# QCopterMV-Camera_Sch.net
KiCad netlist of a schematic drawn in Altium Designer
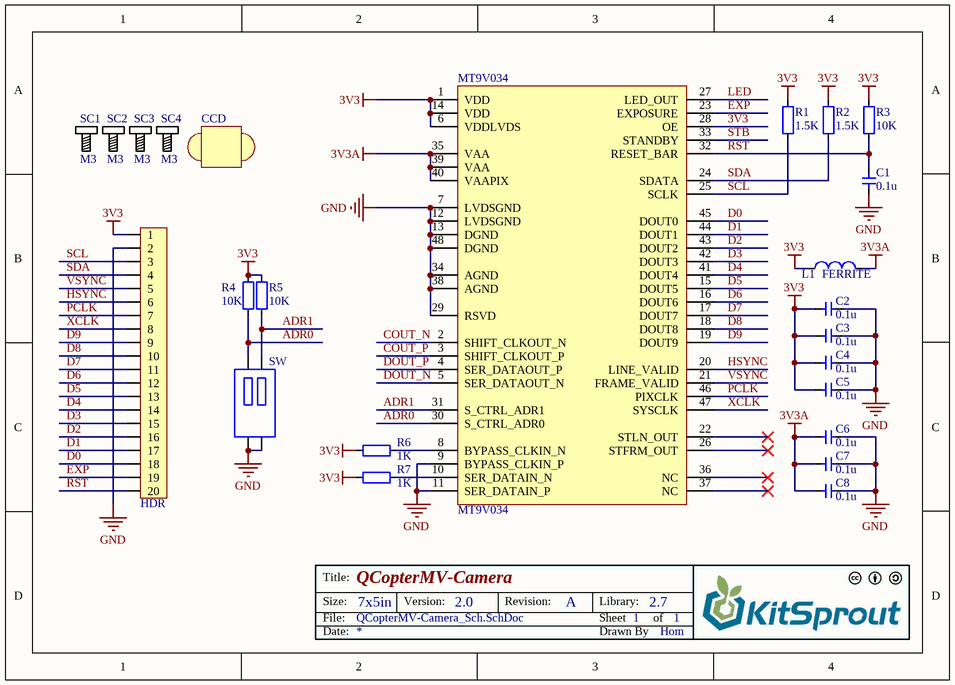
[diagram p0: QCopterMV-Camera_Sch.SchDoc]

(export (version "E")
  (design (tool "Eeschema 10.0.6"))
  (components
    (comp (ref "C1")
      (value "0.1u")
      (footprint "PCB_PassiveCap:CAP_0603")
      (description "Capacitor")
      (fields (field (name "Comment") "Cap_0603"))
      (libsource (lib "SCH_Passive") (part "Cap_0603"))
    )
    (comp (ref "C2")
      (value "0.1u")
      (footprint "PCB_PassiveCap:CAP_0603")
      (description "Capacitor")
      (fields (field (name "Comment") "Cap_0603"))
      (libsource (lib "SCH_Passive") (part "Cap_0603"))
    )
    (comp (ref "C3")
      (value "0.1u")
      (footprint "PCB_PassiveCap:CAP_0603")
      (description "Capacitor")
      (fields (field (name "Comment") "Cap_0603"))
      (libsource (lib "SCH_Passive") (part "Cap_0603"))
    )
    (comp (ref "C4")
      (value "0.1u")
      (footprint "PCB_PassiveCap:CAP_0603")
      (description "Capacitor")
      (fields (field (name "Comment") "Cap_0603"))
      (libsource (lib "SCH_Passive") (part "Cap_0603"))
    )
    (comp (ref "C5")
      (value "0.1u")
      (footprint "PCB_PassiveCap:CAP_0603")
      (description "Capacitor")
      (fields (field (name "Comment") "Cap_0603"))
      (libsource (lib "SCH_Passive") (part "Cap_0603"))
    )
    (comp (ref "C6")
      (value "0.1u")
      (footprint "PCB_PassiveCap:CAP_0603")
      (description "Capacitor")
      (fields (field (name "Comment") "Cap_0603"))
      (libsource (lib "SCH_Passive") (part "Cap_0603"))
    )
    (comp (ref "C7")
      (value "0.1u")
      (footprint "PCB_PassiveCap:CAP_0603")
      (description "Capacitor")
      (fields (field (name "Comment") "Cap_0603"))
      (libsource (lib "SCH_Passive") (part "Cap_0603"))
    )
    (comp (ref "C8")
      (value "0.1u")
      (footprint "PCB_PassiveCap:CAP_0603")
      (description "Capacitor")
      (fields (field (name "Comment") "Cap_0603"))
      (libsource (lib "SCH_Passive") (part "Cap_0603"))
    )
    (comp (ref "CCD")
      (value "CCD")
      (footprint "PCB_Mechanical:CCD_LENS_20MM")
      (libsource (lib "SCH_Mechanical") (part "lensCCD_20"))
    )
    (comp (ref "HDR")
      (value "HDR1x20_1.27")
      (footprint "PCB_ConnectorHDR:HDR1X20_1.27_180")
      (description "Header")
      (libsource (lib "SCH_ConnectorHDR") (part "HDR1x20_1.27"))
    )
    (comp (ref "L1")
      (value "FERRITE")
      (footprint "PCB_PassiveInd:IND_0603")
      (description "Inductor")
      (fields (field (name "Comment") "Ind_0603"))
      (libsource (lib "SCH_Passive") (part "Ind_0603"))
    )
    (comp (ref "MT9V034")
      (value "MT9V034")
      (footprint "PCB_IntegratedCircuit:CLCC_48")
      (description "CMOS")
      (libsource (lib "SCH_IntegratedCircuit") (part "MT9V034"))
    )
    (comp (ref "R1")
      (value "1.5K")
      (footprint "PCB_PassiveRes:RES_0603")
      (description "Resistor")
      (fields (field (name "Comment") "Res_0603"))
      (libsource (lib "SCH_Passive") (part "Res_0603"))
    )
    (comp (ref "R2")
      (value "1.5K")
      (footprint "PCB_PassiveRes:RES_0603")
      (description "Resistor")
      (fields (field (name "Comment") "Res_0603"))
      (libsource (lib "SCH_Passive") (part "Res_0603"))
    )
    (comp (ref "R3")
      (value "10K")
      (footprint "PCB_PassiveRes:RES_0603")
      (description "Resistor")
      (fields (field (name "Comment") "Res_0603"))
      (libsource (lib "SCH_Passive") (part "Res_0603"))
    )
    (comp (ref "R4")
      (value "10K")
      (footprint "PCB_PassiveRes:RES_0603")
      (description "Resistor")
      (fields (field (name "Comment") "Res_0603"))
      (libsource (lib "SCH_Passive") (part "Res_0603"))
    )
    (comp (ref "R5")
      (value "10K")
      (footprint "PCB_PassiveRes:RES_0603")
      (description "Resistor")
      (fields (field (name "Comment") "Res_0603"))
      (libsource (lib "SCH_Passive") (part "Res_0603"))
    )
    (comp (ref "R6")
      (value "1K")
      (footprint "PCB_PassiveRes:RES_0603")
      (description "Resistor")
      (fields (field (name "Comment") "Res_0603"))
      (libsource (lib "") (part "Res_0603_1"))
    )
    (comp (ref "R7")
      (value "1K")
      (footprint "PCB_PassiveRes:RES_0603")
      (description "Resistor")
      (fields (field (name "Comment") "Res_0603"))
      (libsource (lib "") (part "Res_0603_1"))
    )
    (comp (ref "SC1")
      (value "M3")
      (footprint "PCB_Mechanical:SCRREW_M3")
      (description "Screw")
      (libsource (lib "SCH_Mechanical") (part "Screw_M3"))
    )
    (comp (ref "SC2")
      (value "M3")
      (footprint "PCB_Mechanical:SCRREW_M3")
      (description "Screw")
      (libsource (lib "SCH_Mechanical") (part "Screw_M3"))
    )
    (comp (ref "SC3")
      (value "M3")
      (footprint "PCB_Mechanical:SCRREW_M3")
      (description "Screw")
      (libsource (lib "SCH_Mechanical") (part "Screw_M3"))
    )
    (comp (ref "SC4")
      (value "M3")
      (footprint "PCB_Mechanical:SCRREW_M3")
      (description "Screw")
      (libsource (lib "SCH_Mechanical") (part "Screw_M3"))
    )
    (comp (ref "SW")
      (value "SwitchSPST_2P")
      (footprint "PCB_Switch:SwitchSPDT_P2_180")
      (description "Switch")
      (libsource (lib "SCH_Switch") (part "SwitchSPST_2P"))
    )
  )
  (nets
    (net (code "1") (name "/ADR0") (class "Default")
      (node (ref "MT9V034") (pin "30") (pinfunction "S_CTRL_ADR0_30") (pintype "passive"))
      (node (ref "R4") (pin "1") (pinfunction "1_1") (pintype "passive"))
      (node (ref "SW") (pin "1ON") (pinfunction "ON_1ON") (pintype "passive"))
    )
    (net (code "2") (name "/ADR1") (class "Default")
      (node (ref "MT9V034") (pin "31") (pinfunction "S_CTRL_ADR1_31") (pintype "passive"))
      (node (ref "R5") (pin "1") (pinfunction "1_1") (pintype "passive"))
      (node (ref "SW") (pin "2ON") (pinfunction "NO_2ON") (pintype "passive"))
    )
    (net (code "3") (name "/COUT_N") (class "Default")
      (node (ref "MT9V034") (pin "2") (pinfunction "SHIFT_CLKOUT_N_2") (pintype "passive"))
    )
    (net (code "4") (name "/COUT_P") (class "Default")
      (node (ref "MT9V034") (pin "3") (pinfunction "SHIFT_CLKOUT_P_3") (pintype "passive"))
    )
    (net (code "5") (name "/D0") (class "Default")
      (node (ref "HDR") (pin "18") (pinfunction "18_18") (pintype "passive"))
      (node (ref "MT9V034") (pin "45") (pinfunction "DOUT0_45") (pintype "passive"))
    )
    (net (code "6") (name "/D1") (class "Default")
      (node (ref "HDR") (pin "17") (pinfunction "17_17") (pintype "passive"))
      (node (ref "MT9V034") (pin "44") (pinfunction "DOUT1_44") (pintype "passive"))
    )
    (net (code "7") (name "/D2") (class "Default")
      (node (ref "HDR") (pin "16") (pinfunction "16_16") (pintype "passive"))
      (node (ref "MT9V034") (pin "43") (pinfunction "DOUT2_43") (pintype "passive"))
    )
    (net (code "8") (name "/D3") (class "Default")
      (node (ref "HDR") (pin "15") (pinfunction "15_15") (pintype "passive"))
      (node (ref "MT9V034") (pin "42") (pinfunction "DOUT3_42") (pintype "passive"))
    )
    (net (code "9") (name "/D4") (class "Default")
      (node (ref "HDR") (pin "14") (pinfunction "14_14") (pintype "passive"))
      (node (ref "MT9V034") (pin "41") (pinfunction "DOUT4_41") (pintype "passive"))
    )
    (net (code "10") (name "/D5") (class "Default")
      (node (ref "HDR") (pin "13") (pinfunction "13_13") (pintype "passive"))
      (node (ref "MT9V034") (pin "15") (pinfunction "DOUT5_15") (pintype "passive"))
    )
    (net (code "11") (name "/D6") (class "Default")
      (node (ref "HDR") (pin "12") (pinfunction "12_12") (pintype "passive"))
      (node (ref "MT9V034") (pin "16") (pinfunction "DOUT6_16") (pintype "passive"))
    )
    (net (code "12") (name "/D7") (class "Default")
      (node (ref "HDR") (pin "11") (pinfunction "11_11") (pintype "passive"))
      (node (ref "MT9V034") (pin "17") (pinfunction "DOUT7_17") (pintype "passive"))
    )
    (net (code "13") (name "/D8") (class "Default")
      (node (ref "HDR") (pin "10") (pinfunction "10_10") (pintype "passive"))
      (node (ref "MT9V034") (pin "18") (pinfunction "DOUT8_18") (pintype "passive"))
    )
    (net (code "14") (name "/D9") (class "Default")
      (node (ref "HDR") (pin "9") (pinfunction "9_9") (pintype "passive"))
      (node (ref "MT9V034") (pin "19") (pinfunction "DOUT9_19") (pintype "passive"))
    )
    (net (code "15") (name "/DOUT_N") (class "Default")
      (node (ref "MT9V034") (pin "5") (pinfunction "SER_DATAOUT_N_5") (pintype "passive"))
    )
    (net (code "16") (name "/DOUT_P") (class "Default")
      (node (ref "MT9V034") (pin "4") (pinfunction "SER_DATAOUT_P_4") (pintype "passive"))
    )
    (net (code "17") (name "/EXP") (class "Default")
      (node (ref "HDR") (pin "19") (pinfunction "19_19") (pintype "passive"))
      (node (ref "MT9V034") (pin "23") (pinfunction "EXPOSURE_23") (pintype "passive"))
    )
    (net (code "18") (name "/HSYNC") (class "Default")
      (node (ref "HDR") (pin "6") (pinfunction "6_6") (pintype "passive"))
      (node (ref "MT9V034") (pin "20") (pinfunction "LINE_VALID_20") (pintype "passive"))
    )
    (net (code "19") (name "/LED") (class "Default")
      (node (ref "MT9V034") (pin "27") (pinfunction "LED_OUT_27") (pintype "passive"))
    )
    (net (code "20") (name "/PCLK") (class "Default")
      (node (ref "HDR") (pin "7") (pinfunction "7_7") (pintype "passive"))
      (node (ref "MT9V034") (pin "46") (pinfunction "PIXCLK_46") (pintype "passive"))
    )
    (net (code "21") (name "/RST") (class "Default")
      (node (ref "C1") (pin "2") (pinfunction "2_2") (pintype "passive"))
      (node (ref "HDR") (pin "20") (pinfunction "20_20") (pintype "passive"))
      (node (ref "MT9V034") (pin "32") (pinfunction "RESET_BAR_32") (pintype "passive"))
      (node (ref "R3") (pin "1") (pinfunction "1_1") (pintype "passive"))
    )
    (net (code "22") (name "/SCL") (class "Default")
      (node (ref "HDR") (pin "3") (pinfunction "3_3") (pintype "passive"))
      (node (ref "MT9V034") (pin "25") (pinfunction "SCLK_25") (pintype "passive"))
      (node (ref "R1") (pin "1") (pinfunction "1_1") (pintype "passive"))
    )
    (net (code "23") (name "/SDA") (class "Default")
      (node (ref "HDR") (pin "4") (pinfunction "4_4") (pintype "passive"))
      (node (ref "MT9V034") (pin "24") (pinfunction "SDATA_24") (pintype "passive"))
      (node (ref "R2") (pin "1") (pinfunction "1_1") (pintype "passive"))
    )
    (net (code "24") (name "/STB") (class "Default")
      (node (ref "MT9V034") (pin "33") (pinfunction "STANDBY_33") (pintype "passive"))
    )
    (net (code "25") (name "/VSYNC") (class "Default")
      (node (ref "HDR") (pin "5") (pinfunction "5_5") (pintype "passive"))
      (node (ref "MT9V034") (pin "21") (pinfunction "FRAME_VALID_21") (pintype "passive"))
    )
    (net (code "26") (name "/XCLK") (class "Default")
      (node (ref "HDR") (pin "8") (pinfunction "8_8") (pintype "passive"))
      (node (ref "MT9V034") (pin "47") (pinfunction "SYSCLK_47") (pintype "passive"))
    )
    (net (code "27") (name "3V3") (class "Default")
      (node (ref "C2") (pin "2") (pinfunction "2_2") (pintype "passive"))
      (node (ref "C3") (pin "2") (pinfunction "2_2") (pintype "passive"))
      (node (ref "C4") (pin "2") (pinfunction "2_2") (pintype "passive"))
      (node (ref "C5") (pin "2") (pinfunction "2_2") (pintype "passive"))
      (node (ref "HDR") (pin "1") (pinfunction "1_1") (pintype "passive"))
      (node (ref "L1") (pin "1") (pinfunction "1_1") (pintype "passive"))
      (node (ref "MT9V034") (pin "1") (pinfunction "VDD_1") (pintype "passive"))
      (node (ref "MT9V034") (pin "14") (pinfunction "VDD_14") (pintype "passive"))
      (node (ref "MT9V034") (pin "28") (pinfunction "OE_28") (pintype "passive"))
      (node (ref "MT9V034") (pin "6") (pinfunction "VDDLVDS_6") (pintype "passive"))
      (node (ref "R1") (pin "2") (pinfunction "2_2") (pintype "passive"))
      (node (ref "R2") (pin "2") (pinfunction "2_2") (pintype "passive"))
      (node (ref "R3") (pin "2") (pinfunction "2_2") (pintype "passive"))
      (node (ref "R4") (pin "2") (pinfunction "2_2") (pintype "passive"))
      (node (ref "R5") (pin "2") (pinfunction "2_2") (pintype "passive"))
      (node (ref "R6") (pin "2") (pinfunction "2_2") (pintype "passive"))
      (node (ref "R7") (pin "2") (pinfunction "2_2") (pintype "passive"))
    )
    (net (code "28") (name "3V3A") (class "Default")
      (node (ref "C6") (pin "2") (pinfunction "2_2") (pintype "passive"))
      (node (ref "C7") (pin "2") (pinfunction "2_2") (pintype "passive"))
      (node (ref "C8") (pin "2") (pinfunction "2_2") (pintype "passive"))
      (node (ref "L1") (pin "2") (pinfunction "2_2") (pintype "passive"))
      (node (ref "MT9V034") (pin "35") (pinfunction "VAA_35") (pintype "passive"))
      (node (ref "MT9V034") (pin "39") (pinfunction "VAA_39") (pintype "passive"))
      (node (ref "MT9V034") (pin "40") (pinfunction "VAAPIX_40") (pintype "passive"))
    )
    (net (code "29") (name "GND") (class "Default")
      (node (ref "C1") (pin "1") (pinfunction "1_1") (pintype "passive"))
      (node (ref "C2") (pin "1") (pinfunction "1_1") (pintype "passive"))
      (node (ref "C3") (pin "1") (pinfunction "1_1") (pintype "passive"))
      (node (ref "C4") (pin "1") (pinfunction "1_1") (pintype "passive"))
      (node (ref "C5") (pin "1") (pinfunction "1_1") (pintype "passive"))
      (node (ref "C6") (pin "1") (pinfunction "1_1") (pintype "passive"))
      (node (ref "C7") (pin "1") (pinfunction "1_1") (pintype "passive"))
      (node (ref "C8") (pin "1") (pinfunction "1_1") (pintype "passive"))
      (node (ref "HDR") (pin "2") (pinfunction "2_2") (pintype "passive"))
      (node (ref "MT9V034") (pin "11") (pinfunction "SER_DATAIN_P_11") (pintype "passive"))
      (node (ref "MT9V034") (pin "12") (pinfunction "LVDSGND_12") (pintype "passive"))
      (node (ref "MT9V034") (pin "13") (pinfunction "DGND_13") (pintype "passive"))
      (node (ref "MT9V034") (pin "29") (pinfunction "RSVD_29") (pintype "passive"))
      (node (ref "MT9V034") (pin "34") (pinfunction "AGND_34") (pintype "passive"))
      (node (ref "MT9V034") (pin "38") (pinfunction "AGND_38") (pintype "passive"))
      (node (ref "MT9V034") (pin "48") (pinfunction "DGND_48") (pintype "passive"))
      (node (ref "MT9V034") (pin "7") (pinfunction "LVDSGND_7") (pintype "passive"))
      (node (ref "MT9V034") (pin "9") (pinfunction "BYPASS_CLKIN_P_9") (pintype "passive"))
      (node (ref "SW") (pin "1") (pinfunction "COMMON_1") (pintype "passive"))
      (node (ref "SW") (pin "2") (pinfunction "COMMON_2") (pintype "passive"))
    )
    (net (code "30") (name "Net-(MT9V034-BYPASS_CLKIN_N)") (class "Default")
      (node (ref "MT9V034") (pin "8") (pinfunction "BYPASS_CLKIN_N_8") (pintype "passive"))
      (node (ref "R6") (pin "1") (pinfunction "1_1") (pintype "passive"))
    )
    (net (code "31") (name "Net-(MT9V034-SER_DATAIN_N)") (class "Default")
      (node (ref "MT9V034") (pin "10") (pinfunction "SER_DATAIN_N_10") (pintype "passive"))
      (node (ref "R7") (pin "1") (pinfunction "1_1") (pintype "passive"))
    )
    (net (code "32") (name "unconnected-(MT9V034-NC-Pad36)") (class "Default")
      (node (ref "MT9V034") (pin "36") (pinfunction "NC_36") (pintype "passive+no_connect"))
    )
    (net (code "33") (name "unconnected-(MT9V034-NC-Pad37)") (class "Default")
      (node (ref "MT9V034") (pin "37") (pinfunction "NC_37") (pintype "passive+no_connect"))
    )
    (net (code "34") (name "unconnected-(MT9V034-STFRM_OUT-Pad26)") (class "Default")
      (node (ref "MT9V034") (pin "26") (pinfunction "STFRM_OUT_26") (pintype "passive+no_connect"))
    )
    (net (code "35") (name "unconnected-(MT9V034-STLN_OUT-Pad22)") (class "Default")
      (node (ref "MT9V034") (pin "22") (pinfunction "STLN_OUT_22") (pintype "passive+no_connect"))
    )
  )
)
